# owss.net
KiCad netlist of a schematic drawn in EAGLE
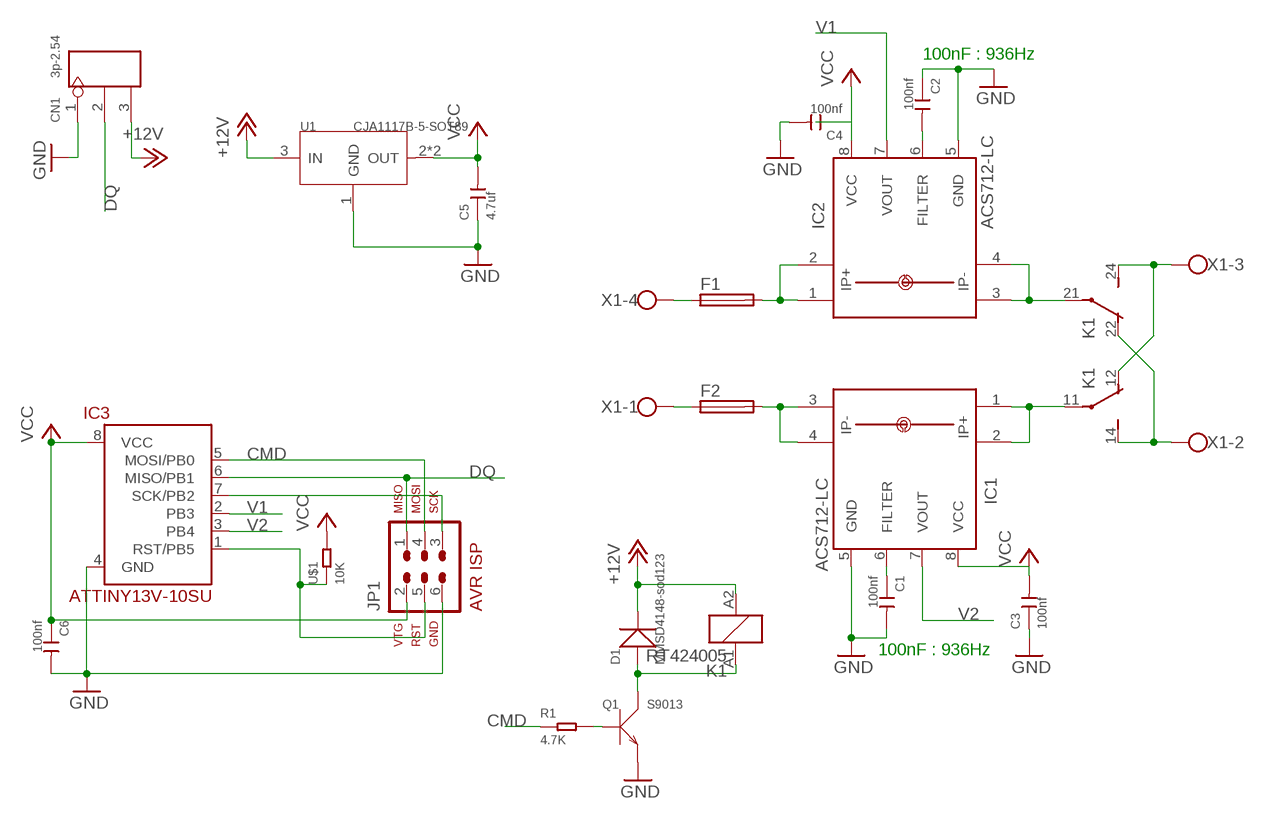
[diagram p0: schematic, sheet 1]

(export (version "E")
  (design (tool "Eeschema 10.0.6"))
  (components
    (comp (ref "C1")
      (value "100nf")
      (footprint "eagle-import:C0805")
      (fields (field (name "MPN") "CC0805KRX7R9BB104"))
      (libsource (lib "eagle-import") (part "CERAMIC-100NF-50V-10%-X7R(0805)"))
    )
    (comp (ref "C2")
      (value "100nf")
      (footprint "eagle-import:C0805")
      (fields (field (name "MPN") "CC0805KRX7R9BB104"))
      (libsource (lib "eagle-import") (part "CERAMIC-100NF-50V-10%-X7R(0805)"))
    )
    (comp (ref "C3")
      (value "100nf")
      (footprint "eagle-import:C0805")
      (fields (field (name "MPN") "CC0805KRX7R9BB104"))
      (libsource (lib "eagle-import") (part "CERAMIC-100NF-50V-10%-X7R(0805)"))
    )
    (comp (ref "C4")
      (value "100nf")
      (footprint "eagle-import:C0805")
      (fields (field (name "MPN") "CC0805KRX7R9BB104"))
      (libsource (lib "eagle-import") (part "CERAMIC-100NF-50V-10%-X7R(0805)"))
    )
    (comp (ref "C5")
      (value "4.7uf")
      (footprint "eagle-import:C0805")
      (fields (field (name "MPN") "CC0805KKX5R8BB475"))
      (libsource (lib "eagle-import") (part "CERAMIC-4.7UF-25V-10%-X5R(0805)"))
    )
    (comp (ref "C6")
      (value "100nf")
      (footprint "eagle-import:C0805")
      (fields (field (name "MPN") "CC0805KRX7R9BB104"))
      (libsource (lib "eagle-import") (part "CERAMIC-100NF-50V-10%-X7R(0805)"))
    )
    (comp (ref "CN1")
      (value "3p-2.54")
      (footprint "eagle-import:H3-2.54")
      (libsource (lib "eagle-import") (part "DIP-BLACK-MALE-HEADER-VERT(3P-2.54)"))
    )
    (comp (ref "D1")
      (value "MMSD4148-sod123")
      (footprint "eagle-import:SOD-123")
      (fields (field (name "MPN") "MMSD4148"))
      (libsource (lib "eagle-import") (part "SMD-DIODE-100V-200MA(SOD-123)"))
    )
    (comp (ref "F1")
      (value "TE5")
      (footprint "eagle-import:TE5")
      (libsource (lib "eagle-import") (part "TE5"))
    )
    (comp (ref "F2")
      (value "TE5")
      (footprint "eagle-import:TE5")
      (libsource (lib "eagle-import") (part "TE5"))
    )
    (comp (ref "IC1")
      (value "ACS712-LC")
      (footprint "eagle-import:SOIC8")
      (libsource (lib "eagle-import") (part "ACS712-LC"))
    )
    (comp (ref "IC2")
      (value "ACS712-LC")
      (footprint "eagle-import:SOIC8")
      (libsource (lib "eagle-import") (part "ACS712-LC"))
    )
    (comp (ref "IC3")
      (value "ATTINY13V-10SU")
      (footprint "eagle-import:SOIC8")
      (libsource (lib "eagle-import") (part "ATTINY13V-10SU"))
    )
    (comp (ref "JP1")
      (value "AVR-ISP-6")
      (footprint "eagle-import:AVR-ISP-6")
      (libsource (lib "eagle-import") (part "AVR-ISP-6"))
    )
    (comp (ref "K1")
      (value "RT424005")
      (footprint "eagle-import:RT2C_O")
      (libsource (lib "eagle-import") (part "RT42?4005"))
    )
    (comp (ref "Q1")
      (value "S9013")
      (footprint "eagle-import:SOT-23")
      (libsource (lib "eagle-import") (part "SMD-TRANSISTORS-NPN-25V-500MA-S9013(SOT-23)"))
    )
    (comp (ref "R1")
      (value "4.7K")
      (footprint "eagle-import:R0805")
      (fields (field (name "MPN") "RC0805JR-074K7L"))
      (libsource (lib "eagle-import") (part "SMD-RES-4.7K-5%-1/8W(0805)"))
    )
    (comp (ref "U$1")
      (value "10K")
      (footprint "eagle-import:R0805")
      (fields (field (name "MPN") "RC0805FR-0710KL"))
      (libsource (lib "eagle-import") (part "SMD-RES-10K-1%-1/8W(0805)"))
    )
    (comp (ref "U1")
      (value "CJA1117B-5-SOT89")
      (footprint "eagle-import:SOT-89")
      (fields (field (name "MPN") "CJA1117B-3.3"))
      (libsource (lib "eagle-import") (part "PMIC-CJA1117B-3.3(SOT-89)"))
    )
    (comp (ref "X1")
      (value "W237-4")
      (footprint "eagle-import:W237-4")
      (libsource (lib "eagle-import") (part "W237-4"))
    )
  )
  (nets
    (net (code "1") (name "+12V") (class "Default")
      (node (ref "CN1") (pin "3") (pinfunction "P$3_3") (pintype "bidirectional"))
      (node (ref "D1") (pin "-") (pinfunction "-_-") (pintype "passive"))
      (node (ref "K1") (pin "A2") (pinfunction "2_A2") (pintype "passive"))
      (node (ref "U1") (pin "3") (pinfunction "IN_3") (pintype "bidirectional"))
    )
    (net (code "2") (name "/CMD") (class "Default")
      (node (ref "IC3") (pin "5") (pinfunction "MOSI/PB0_5") (pintype "bidirectional"))
      (node (ref "JP1") (pin "4") (pinfunction "4_4") (pintype "passive"))
      (node (ref "R1") (pin "1") (pinfunction "1_1") (pintype "passive"))
    )
    (net (code "3") (name "/DQ") (class "Default")
      (node (ref "CN1") (pin "2") (pinfunction "P$2_2") (pintype "bidirectional"))
      (node (ref "IC3") (pin "6") (pinfunction "MISO/PB1_6") (pintype "bidirectional"))
      (node (ref "JP1") (pin "1") (pinfunction "1_1") (pintype "passive"))
    )
    (net (code "4") (name "/V1") (class "Default")
      (node (ref "IC2") (pin "7") (pinfunction "VOUT_7") (pintype "output"))
      (node (ref "IC3") (pin "2") (pinfunction "PB3_2") (pintype "bidirectional"))
    )
    (net (code "5") (name "/V2") (class "Default")
      (node (ref "IC1") (pin "7") (pinfunction "VOUT_7") (pintype "output"))
      (node (ref "IC3") (pin "3") (pinfunction "PB4_3") (pintype "bidirectional"))
    )
    (net (code "6") (name "GND") (class "Default")
      (node (ref "C1") (pin "2") (pinfunction "2_2") (pintype "passive"))
      (node (ref "C2") (pin "1") (pinfunction "1_1") (pintype "passive"))
      (node (ref "C3") (pin "1") (pinfunction "1_1") (pintype "passive"))
      (node (ref "C4") (pin "2") (pinfunction "2_2") (pintype "passive"))
      (node (ref "C5") (pin "1") (pinfunction "1_1") (pintype "passive"))
      (node (ref "C6") (pin "2") (pinfunction "2_2") (pintype "passive"))
      (node (ref "CN1") (pin "1") (pinfunction "P$1_1") (pintype "bidirectional"))
      (node (ref "IC1") (pin "5") (pinfunction "GND_5") (pintype "power_in"))
      (node (ref "IC2") (pin "5") (pinfunction "GND_5") (pintype "power_in"))
      (node (ref "IC3") (pin "4") (pinfunction "GND_4") (pintype "power_in"))
      (node (ref "JP1") (pin "6") (pinfunction "6_6") (pintype "passive"))
      (node (ref "Q1") (pin "2") (pinfunction "E_2") (pintype "passive"))
      (node (ref "U1") (pin "1") (pinfunction "GND_1") (pintype "bidirectional"))
    )
    (net (code "7") (name "Net-(IC1-FILTER)") (class "Default")
      (node (ref "C1") (pin "1") (pinfunction "1_1") (pintype "passive"))
      (node (ref "IC1") (pin "6") (pinfunction "FILTER_6") (pintype "bidirectional"))
    )
    (net (code "8") (name "Net-(IC1-IP+)") (class "Default")
      (node (ref "IC1") (pin "1") (pinfunction "IP+_1") (pintype "passive"))
      (node (ref "IC1") (pin "2") (pinfunction "IP+1_2") (pintype "passive"))
      (node (ref "K1") (pin "11") (pinfunction "P_11") (pintype "passive"))
    )
    (net (code "9") (name "Net-(IC1-IP-)") (class "Default")
      (node (ref "F2") (pin "2") (pinfunction "2_2") (pintype "passive"))
      (node (ref "IC1") (pin "3") (pinfunction "IP-_3") (pintype "passive"))
      (node (ref "IC1") (pin "4") (pinfunction "IP-1_4") (pintype "passive"))
    )
    (net (code "10") (name "Net-(IC2-FILTER)") (class "Default")
      (node (ref "C2") (pin "2") (pinfunction "2_2") (pintype "passive"))
      (node (ref "IC2") (pin "6") (pinfunction "FILTER_6") (pintype "bidirectional"))
    )
    (net (code "11") (name "Net-(IC2-IP+)") (class "Default")
      (node (ref "F1") (pin "2") (pinfunction "2_2") (pintype "passive"))
      (node (ref "IC2") (pin "1") (pinfunction "IP+_1") (pintype "passive"))
      (node (ref "IC2") (pin "2") (pinfunction "IP+1_2") (pintype "passive"))
    )
    (net (code "12") (name "Net-(IC2-IP-)") (class "Default")
      (node (ref "IC2") (pin "3") (pinfunction "IP-_3") (pintype "passive"))
      (node (ref "IC2") (pin "4") (pinfunction "IP-1_4") (pintype "passive"))
      (node (ref "K1") (pin "21") (pinfunction "P_21") (pintype "passive"))
    )
    (net (code "13") (name "Net-(IC3-RST{slash}PB5)") (class "Default")
      (node (ref "IC3") (pin "1") (pinfunction "RST/PB5_1") (pintype "bidirectional"))
      (node (ref "JP1") (pin "5") (pinfunction "5_5") (pintype "passive"))
      (node (ref "U$1") (pin "1") (pinfunction "1_1") (pintype "passive"))
    )
    (net (code "14") (name "Net-(IC3-SCK{slash}PB2)") (class "Default")
      (node (ref "IC3") (pin "7") (pinfunction "SCK/PB2_7") (pintype "bidirectional"))
      (node (ref "JP1") (pin "3") (pinfunction "3_3") (pintype "passive"))
    )
    (net (code "15") (name "Net-(K1A-1)") (class "Default")
      (node (ref "D1") (pin "+") (pinfunction "+_+") (pintype "passive"))
      (node (ref "K1") (pin "A1") (pinfunction "1_A1") (pintype "passive"))
      (node (ref "Q1") (pin "3") (pinfunction "C_3") (pintype "passive"))
    )
    (net (code "16") (name "Net-(K1B-O)") (class "Default")
      (node (ref "K1") (pin "12") (pinfunction "O_12") (pintype "passive"))
      (node (ref "K1") (pin "24") (pinfunction "S_24") (pintype "passive"))
      (node (ref "X1") (pin "3") (pinfunction "KL_3") (pintype "passive"))
    )
    (net (code "17") (name "Net-(K1B-S)") (class "Default")
      (node (ref "K1") (pin "14") (pinfunction "S_14") (pintype "passive"))
      (node (ref "K1") (pin "22") (pinfunction "O_22") (pintype "passive"))
      (node (ref "X1") (pin "2") (pinfunction "KL_2") (pintype "passive"))
    )
    (net (code "18") (name "Net-(Q1-B)") (class "Default")
      (node (ref "Q1") (pin "1") (pinfunction "B_1") (pintype "passive"))
      (node (ref "R1") (pin "2") (pinfunction "2_2") (pintype "passive"))
    )
    (net (code "19") (name "Net-(X1A-KL)") (class "Default")
      (node (ref "F2") (pin "1") (pinfunction "1_1") (pintype "passive"))
      (node (ref "X1") (pin "1") (pinfunction "KL_1") (pintype "passive"))
    )
    (net (code "20") (name "Net-(X1D-KL)") (class "Default")
      (node (ref "F1") (pin "1") (pinfunction "1_1") (pintype "passive"))
      (node (ref "X1") (pin "4") (pinfunction "KL_4") (pintype "passive"))
    )
    (net (code "21") (name "VCC") (class "Default")
      (node (ref "C3") (pin "2") (pinfunction "2_2") (pintype "passive"))
      (node (ref "C4") (pin "1") (pinfunction "1_1") (pintype "passive"))
      (node (ref "C5") (pin "2") (pinfunction "2_2") (pintype "passive"))
      (node (ref "C6") (pin "1") (pinfunction "1_1") (pintype "passive"))
      (node (ref "IC1") (pin "8") (pinfunction "VCC_8") (pintype "power_in"))
      (node (ref "IC2") (pin "8") (pinfunction "VCC_8") (pintype "power_in"))
      (node (ref "IC3") (pin "8") (pinfunction "VCC_8") (pintype "power_in"))
      (node (ref "JP1") (pin "2") (pinfunction "2_2") (pintype "passive"))
      (node (ref "U$1") (pin "2") (pinfunction "2_2") (pintype "passive"))
      (node (ref "U1") (pin "2") (pinfunction "OUT_2") (pintype "bidirectional"))
      (node (ref "U1") (pin "4") (pinfunction "OUT_4") (pintype "bidirectional"))
    )
  )
)
